# Glucose_Meter_Rev2.net
KiCad netlist of a schematic drawn in EAGLE
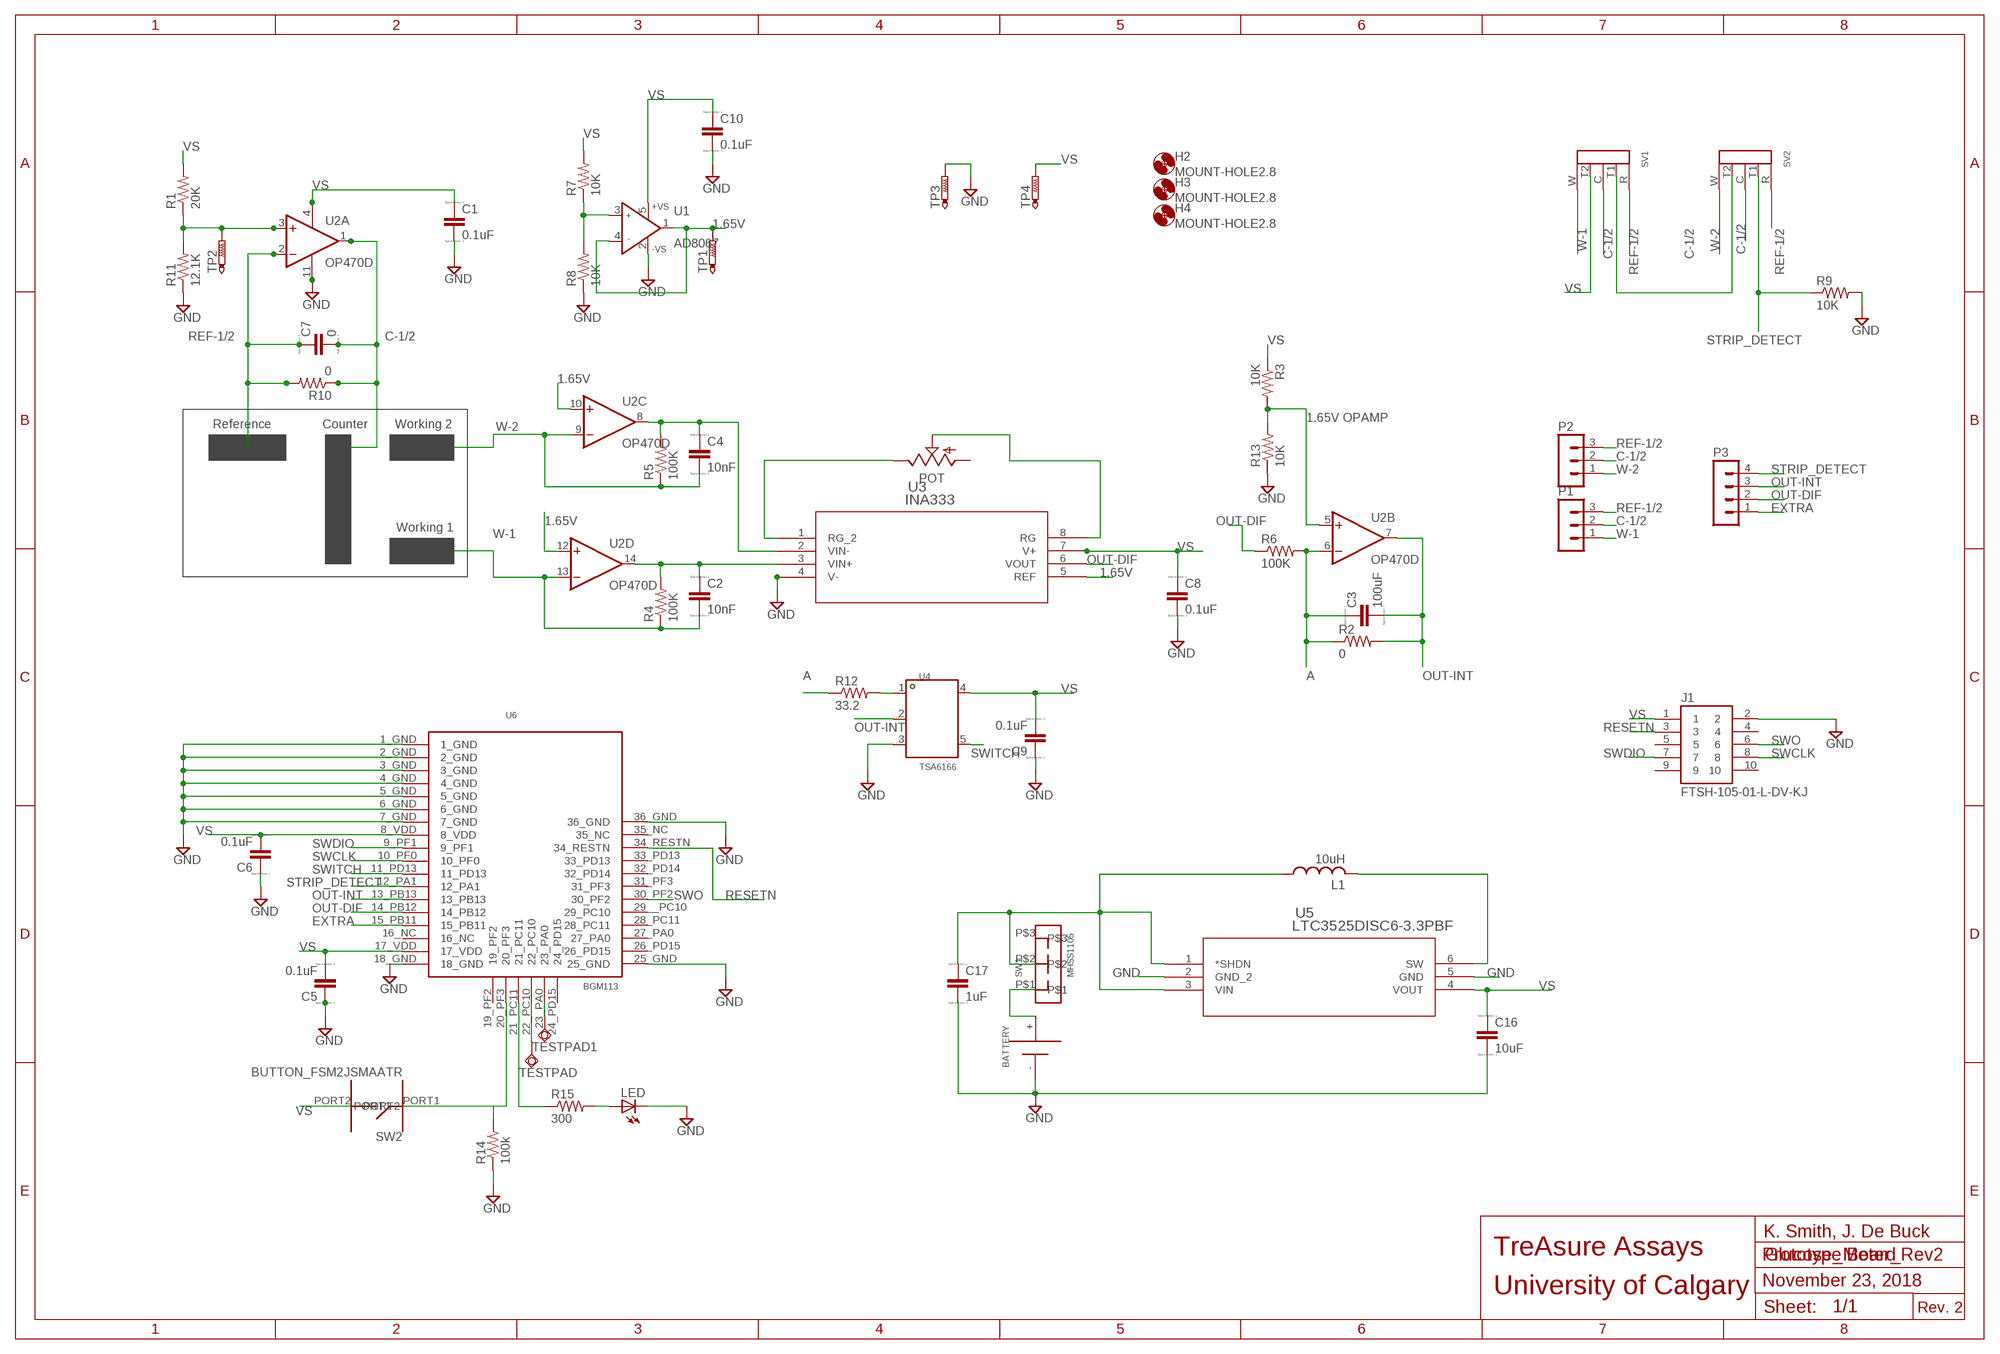
[diagram p0: schematic, sheet 1]

(export (version "E")
  (design (tool "Eeschema 10.0.6"))
  (components
    (comp (ref "BATTERY")
      (value "SMTU2032")
      (footprint "eagle-import:SMTU2032")
      (libsource (lib "eagle-import") (part "SMTU2032"))
    )
    (comp (ref "C1")
      (value "0.1uF")
      (footprint "eagle-import:C0805")
      (libsource (lib "eagle-import") (part "C"))
    )
    (comp (ref "C2")
      (value "10nF")
      (footprint "eagle-import:C0805")
      (libsource (lib "eagle-import") (part "C"))
    )
    (comp (ref "C3")
      (value "100uF")
      (footprint "eagle-import:C1210")
      (libsource (lib "eagle-import") (part "CC1210"))
    )
    (comp (ref "C4")
      (value "10nF")
      (footprint "eagle-import:C0805")
      (libsource (lib "eagle-import") (part "C"))
    )
    (comp (ref "C5")
      (value "0.1uF")
      (footprint "eagle-import:C0805")
      (libsource (lib "eagle-import") (part "C"))
    )
    (comp (ref "C6")
      (value "0.1uF")
      (footprint "eagle-import:C0805")
      (libsource (lib "eagle-import") (part "C"))
    )
    (comp (ref "C7") (value "0") (footprint "eagle-import:C0805") (libsource (lib "eagle-import") (part "C")))
    (comp (ref "C8")
      (value "0.1uF")
      (footprint "eagle-import:C0805")
      (libsource (lib "eagle-import") (part "C"))
    )
    (comp (ref "C9")
      (value "0.1uF")
      (footprint "eagle-import:C0805")
      (libsource (lib "eagle-import") (part "C"))
    )
    (comp (ref "C10")
      (value "0.1uF")
      (footprint "eagle-import:C0805")
      (libsource (lib "eagle-import") (part "C"))
    )
    (comp (ref "C16")
      (value "10uF")
      (footprint "eagle-import:C0805")
      (libsource (lib "eagle-import") (part "C"))
    )
    (comp (ref "C17")
      (value "1uF")
      (footprint "eagle-import:C0805")
      (libsource (lib "eagle-import") (part "C"))
    )
    (comp (ref "H2")
      (value "MOUNT-HOLE2.8")
      (footprint "eagle-import:2,8")
      (libsource (lib "eagle-import") (part "MOUNT-HOLE2.8"))
    )
    (comp (ref "H3")
      (value "MOUNT-HOLE2.8")
      (footprint "eagle-import:2,8")
      (libsource (lib "eagle-import") (part "MOUNT-HOLE2.8"))
    )
    (comp (ref "H4")
      (value "MOUNT-HOLE2.8")
      (footprint "eagle-import:2,8")
      (libsource (lib "eagle-import") (part "MOUNT-HOLE2.8"))
    )
    (comp (ref "J1")
      (value "FTSH-105-01-L-DV-KJ")
      (footprint "eagle-import:SAMTEC_FTSH-105-01-L-DV-K")
      (fields (field (name "MF") "Samtec Inc.") (field (name "MP") "FTSH-105-01-L-DV-K"))
      (libsource (lib "eagle-import") (part "FTSH-105-01-L-DV-KJ"))
    )
    (comp (ref "L1")
      (value "10uH")
      (footprint "eagle-import:L3225M")
      (libsource (lib "eagle-import") (part "L-USL3225M"))
    )
    (comp (ref "LED")
      (value "LED3MM")
      (footprint "eagle-import:LED3MM")
      (libsource (lib "eagle-import") (part "LED3MM"))
    )
    (comp (ref "P1")
      (value "MA03-1")
      (footprint "eagle-import:MA03-1")
      (libsource (lib "eagle-import") (part "MA03-1"))
    )
    (comp (ref "P2")
      (value "MA03-1")
      (footprint "eagle-import:MA03-1")
      (libsource (lib "eagle-import") (part "MA03-1"))
    )
    (comp (ref "P3")
      (value "MA04-1")
      (footprint "eagle-import:MA04-1")
      (libsource (lib "eagle-import") (part "MA04-1"))
    )
    (comp (ref "POT")
      (value "TRIM_US-RJ9W")
      (footprint "eagle-import:RJ9W")
      (libsource (lib "eagle-import") (part "TRIM_US-RJ9W"))
    )
    (comp (ref "R1")
      (value "20K")
      (footprint "eagle-import:R0805")
      (libsource (lib "eagle-import") (part "R-US_R0805"))
    )
    (comp (ref "R2")
      (value "0")
      (footprint "eagle-import:R0805")
      (libsource (lib "eagle-import") (part "R-US_R0805"))
    )
    (comp (ref "R3")
      (value "10K")
      (footprint "eagle-import:R0805")
      (libsource (lib "eagle-import") (part "R-US_R0805"))
    )
    (comp (ref "R4")
      (value "100K")
      (footprint "eagle-import:R0805")
      (libsource (lib "eagle-import") (part "R-US_R0805"))
    )
    (comp (ref "R5")
      (value "100K")
      (footprint "eagle-import:R0805")
      (libsource (lib "eagle-import") (part "R-US_R0805"))
    )
    (comp (ref "R6")
      (value "100K")
      (footprint "eagle-import:R0805")
      (libsource (lib "eagle-import") (part "R-US_R0805"))
    )
    (comp (ref "R7")
      (value "10K")
      (footprint "eagle-import:R0805")
      (libsource (lib "eagle-import") (part "R-US_R0805"))
    )
    (comp (ref "R8")
      (value "10K")
      (footprint "eagle-import:R0805")
      (libsource (lib "eagle-import") (part "R-US_R0805"))
    )
    (comp (ref "R9")
      (value "10K")
      (footprint "eagle-import:R0805")
      (libsource (lib "eagle-import") (part "R-US_R0805"))
    )
    (comp (ref "R10")
      (value "0")
      (footprint "eagle-import:R0805")
      (libsource (lib "eagle-import") (part "R-US_R0805"))
    )
    (comp (ref "R11")
      (value "12.1K")
      (footprint "eagle-import:R0805")
      (libsource (lib "eagle-import") (part "R-US_R0805"))
    )
    (comp (ref "R12")
      (value "33.2")
      (footprint "eagle-import:R0805")
      (libsource (lib "eagle-import") (part "R-US_R0805"))
    )
    (comp (ref "R13")
      (value "10K")
      (footprint "eagle-import:R0805")
      (libsource (lib "eagle-import") (part "R-US_R0805"))
    )
    (comp (ref "R14")
      (value "100k")
      (footprint "eagle-import:R0805")
      (libsource (lib "eagle-import") (part "R-US_R0805"))
    )
    (comp (ref "R15")
      (value "300")
      (footprint "eagle-import:R0805")
      (libsource (lib "eagle-import") (part "R-US_R0805"))
    )
    (comp (ref "SV1")
      (value "SW-JS-05")
      (footprint "eagle-import:SW-JS-05")
      (libsource (lib "eagle-import") (part "SW-JS-05"))
    )
    (comp (ref "SV2")
      (value "SW-JS-05")
      (footprint "eagle-import:SW-JS-05")
      (libsource (lib "eagle-import") (part "SW-JS-05"))
    )
    (comp (ref "SW1")
      (value "MHSS1105")
      (footprint "eagle-import:MHSS1105")
      (libsource (lib "eagle-import") (part "MHSS1105"))
    )
    (comp (ref "SW2")
      (value "BUTTON_FSM2JSMAATR")
      (footprint "eagle-import:BUTTON_FSM2JSMAATR")
      (libsource (lib "eagle-import") (part "BUTTON_FSM2JSMAATR"))
    )
    (comp (ref "TESTPAD")
      (value "TPSQTP06R")
      (footprint "eagle-import:TP06R")
      (libsource (lib "eagle-import") (part "TPSQTP06R"))
    )
    (comp (ref "TESTPAD1")
      (value "TPSQTP06R")
      (footprint "eagle-import:TP06R")
      (libsource (lib "eagle-import") (part "TPSQTP06R"))
    )
    (comp (ref "TP1")
      (value "PTR1PAD1-13")
      (footprint "eagle-import:P1-13")
      (libsource (lib "eagle-import") (part "PTR1PAD1-13"))
    )
    (comp (ref "TP2")
      (value "PTR1PAD1-13")
      (footprint "eagle-import:P1-13")
      (libsource (lib "eagle-import") (part "PTR1PAD1-13"))
    )
    (comp (ref "TP3")
      (value "PTR1PAD1-13")
      (footprint "eagle-import:P1-13")
      (libsource (lib "eagle-import") (part "PTR1PAD1-13"))
    )
    (comp (ref "TP4")
      (value "PTR1PAD1-13")
      (footprint "eagle-import:P1-13")
      (libsource (lib "eagle-import") (part "PTR1PAD1-13"))
    )
    (comp (ref "U1")
      (value "AD8067")
      (footprint "eagle-import:SOT23-5")
      (fields (field (name "MF") "ALTERA CORPORATION") (field (name "MPN") "AD8067ARTZ-REEL7"))
      (libsource (lib "eagle-import") (part "AD8067"))
    )
    (comp (ref "U2")
      (value "OP470D")
      (footprint "eagle-import:SO14")
      (libsource (lib "eagle-import") (part "OP470D"))
    )
    (comp (ref "U3")
      (value "INA333")
      (footprint "eagle-import:DGK8")
      (fields
        (field (name "MANUFACTURER") "Texas Instruments")
        (field (name "MANUFACTURER_PART_NUMBER") "ina333_dgk_8")
      )
      (libsource (lib "eagle-import") (part "INA333_DGK_8"))
    )
    (comp (ref "U4")
      (value "TSA6166")
      (footprint "eagle-import:SOT23-5")
      (libsource (lib "eagle-import") (part "TSA6166"))
    )
    (comp (ref "U5")
      (value "LTC3525DISC6-3.3PBF")
      (footprint "eagle-import:SC70-SC6")
      (fields (field (name "MANUFACTURER_PART_NUMBER") "ltc3525disc6-3.3#pbf"))
      (libsource (lib "eagle-import") (part "LTC3525DISC6-3.3PBF"))
    )
    (comp (ref "U6")
      (value "BGM113")
      (footprint "eagle-import:BGM113")
      (libsource (lib "eagle-import") (part "BGM113"))
    )
  )
  (nets
    (net (code "1") (name "/1.65V") (class "Default")
      (node (ref "TP1") (pin "TP") (pinfunction "TP_TP") (pintype "input"))
      (node (ref "U1") (pin "1") (pinfunction "OUT_1") (pintype "output"))
      (node (ref "U1") (pin "4") (pinfunction "IN-_4") (pintype "input"))
      (node (ref "U2") (pin "10") (pinfunction "+IN_10") (pintype "input"))
      (node (ref "U2") (pin "12") (pinfunction "+IN_12") (pintype "input"))
      (node (ref "U3") (pin "5") (pinfunction "REF_5") (pintype "passive"))
    )
    (net (code "2") (name "/A") (class "Default")
      (node (ref "C3") (pin "1") (pinfunction "1_1") (pintype "passive"))
      (node (ref "R12") (pin "1") (pinfunction "1_1") (pintype "passive"))
      (node (ref "R2") (pin "1") (pinfunction "1_1") (pintype "passive"))
      (node (ref "R6") (pin "2") (pinfunction "2_2") (pintype "passive"))
      (node (ref "U2") (pin "6") (pinfunction "-IN_6") (pintype "input"))
    )
    (net (code "3") (name "/C-1{slash}2") (class "Default")
      (node (ref "C7") (pin "2") (pinfunction "2_2") (pintype "passive"))
      (node (ref "P1") (pin "2") (pinfunction "2_2") (pintype "passive"))
      (node (ref "P2") (pin "2") (pinfunction "2_2") (pintype "passive"))
      (node (ref "R10") (pin "1") (pinfunction "1_1") (pintype "passive"))
      (node (ref "SV1") (pin "C") (pinfunction "C_C") (pintype "bidirectional"))
      (node (ref "SV2") (pin "C") (pinfunction "C_C") (pintype "bidirectional"))
      (node (ref "U2") (pin "1") (pinfunction "OUT_1") (pintype "output"))
    )
    (net (code "4") (name "/EXTRA") (class "Default")
      (node (ref "P3") (pin "1") (pinfunction "1_1") (pintype "passive"))
      (node (ref "U6") (pin "15_PB11") (pinfunction "15_PB11_15_PB11") (pintype "bidirectional"))
    )
    (net (code "5") (name "/OUT-DIF") (class "Default")
      (node (ref "P3") (pin "2") (pinfunction "2_2") (pintype "passive"))
      (node (ref "R6") (pin "1") (pinfunction "1_1") (pintype "passive"))
      (node (ref "U3") (pin "6") (pinfunction "VOUT_6") (pintype "output"))
      (node (ref "U6") (pin "14_PB12") (pinfunction "14_PB12_14_PB12") (pintype "bidirectional"))
    )
    (net (code "6") (name "/OUT-INT") (class "Default")
      (node (ref "C3") (pin "2") (pinfunction "2_2") (pintype "passive"))
      (node (ref "P3") (pin "3") (pinfunction "3_3") (pintype "passive"))
      (node (ref "R2") (pin "2") (pinfunction "2_2") (pintype "passive"))
      (node (ref "U2") (pin "7") (pinfunction "OUT_7") (pintype "output"))
      (node (ref "U4") (pin "2") (pinfunction "B_2") (pintype "bidirectional"))
      (node (ref "U6") (pin "13_PB13") (pinfunction "13_PB13_13_PB13") (pintype "bidirectional"))
    )
    (net (code "7") (name "/REF-1{slash}2") (class "Default")
      (node (ref "C7") (pin "1") (pinfunction "1_1") (pintype "passive"))
      (node (ref "P1") (pin "3") (pinfunction "3_3") (pintype "passive"))
      (node (ref "P2") (pin "3") (pinfunction "3_3") (pintype "passive"))
      (node (ref "R10") (pin "2") (pinfunction "2_2") (pintype "passive"))
      (node (ref "SV1") (pin "R") (pinfunction "R_R") (pintype "bidirectional"))
      (node (ref "SV2") (pin "R") (pinfunction "R_R") (pintype "bidirectional"))
      (node (ref "U2") (pin "2") (pinfunction "-IN_2") (pintype "input"))
    )
    (net (code "8") (name "/RESETN") (class "Default")
      (node (ref "J1") (pin "3") (pinfunction "3_3") (pintype "passive"))
      (node (ref "U6") (pin "34_RESTN") (pinfunction "34_RESTN_34_RESTN") (pintype "bidirectional"))
    )
    (net (code "9") (name "/STRIP_DETECT") (class "Default")
      (node (ref "P3") (pin "4") (pinfunction "4_4") (pintype "passive"))
      (node (ref "R9") (pin "1") (pinfunction "1_1") (pintype "passive"))
      (node (ref "SV2") (pin "T1") (pinfunction "T1_T1") (pintype "bidirectional"))
      (node (ref "U6") (pin "12_PA1") (pinfunction "12_PA1_12_PA1") (pintype "bidirectional"))
    )
    (net (code "10") (name "/SWCLK") (class "Default")
      (node (ref "J1") (pin "8") (pinfunction "8_8") (pintype "passive"))
      (node (ref "U6") (pin "10_PF0") (pinfunction "10_PF0_10_PF0") (pintype "bidirectional"))
    )
    (net (code "11") (name "/SWDIO") (class "Default")
      (node (ref "J1") (pin "7") (pinfunction "7_7") (pintype "passive"))
      (node (ref "U6") (pin "9_PF1") (pinfunction "9_PF1_9_PF1") (pintype "bidirectional"))
    )
    (net (code "12") (name "/SWITCH") (class "Default")
      (node (ref "U4") (pin "5") (pinfunction "ON/OFF_5") (pintype "bidirectional"))
      (node (ref "U6") (pin "11_PD13") (pinfunction "11_PD13_11_PD13") (pintype "bidirectional"))
    )
    (net (code "13") (name "/SWO") (class "Default")
      (node (ref "J1") (pin "6") (pinfunction "6_6") (pintype "passive"))
      (node (ref "U6") (pin "30_PF2") (pinfunction "30_PF2_30_PF2") (pintype "bidirectional"))
    )
    (net (code "14") (name "/VS") (class "Default")
      (node (ref "C1") (pin "1") (pinfunction "1_1") (pintype "passive"))
      (node (ref "C10") (pin "1") (pinfunction "1_1") (pintype "passive"))
      (node (ref "C16") (pin "1") (pinfunction "1_1") (pintype "passive"))
      (node (ref "C5") (pin "2") (pinfunction "2_2") (pintype "passive"))
      (node (ref "C6") (pin "2") (pinfunction "2_2") (pintype "passive"))
      (node (ref "C8") (pin "1") (pinfunction "1_1") (pintype "passive"))
      (node (ref "C9") (pin "2") (pinfunction "2_2") (pintype "passive"))
      (node (ref "J1") (pin "1") (pinfunction "1_1") (pintype "passive"))
      (node (ref "R1") (pin "2") (pinfunction "2_2") (pintype "passive"))
      (node (ref "R3") (pin "1") (pinfunction "1_1") (pintype "passive"))
      (node (ref "R7") (pin "2") (pinfunction "2_2") (pintype "passive"))
      (node (ref "SV1") (pin "T2") (pinfunction "T2_T2") (pintype "bidirectional"))
      (node (ref "SW2") (pin "PORT2") (pinfunction "PORT2_PORT2") (pintype "bidirectional"))
      (node (ref "TP4") (pin "TP") (pinfunction "TP_TP") (pintype "input"))
      (node (ref "U1") (pin "5") (pinfunction "+VS_5") (pintype "input"))
      (node (ref "U2") (pin "4") (pinfunction "V+_4") (pintype "power_in"))
      (node (ref "U3") (pin "7") (pinfunction "V+_7") (pintype "power_in"))
      (node (ref "U4") (pin "4") (pinfunction "VS_4") (pintype "bidirectional"))
      (node (ref "U5") (pin "4") (pinfunction "VOUT_4") (pintype "output"))
      (node (ref "U6") (pin "17_VDD") (pinfunction "17_VDD_17_VDD") (pintype "bidirectional"))
      (node (ref "U6") (pin "8_VDD") (pinfunction "8_VDD_8_VDD") (pintype "bidirectional"))
    )
    (net (code "15") (name "/W-1") (class "Default")
      (node (ref "C2") (pin "2") (pinfunction "2_2") (pintype "passive"))
      (node (ref "P1") (pin "1") (pinfunction "1_1") (pintype "passive"))
      (node (ref "R4") (pin "1") (pinfunction "1_1") (pintype "passive"))
      (node (ref "SV1") (pin "W") (pinfunction "W_W") (pintype "bidirectional"))
      (node (ref "U2") (pin "13") (pinfunction "-IN_13") (pintype "input"))
    )
    (net (code "16") (name "/W-2") (class "Default")
      (node (ref "C4") (pin "2") (pinfunction "2_2") (pintype "passive"))
      (node (ref "P2") (pin "1") (pinfunction "1_1") (pintype "passive"))
      (node (ref "R5") (pin "1") (pinfunction "1_1") (pintype "passive"))
      (node (ref "SV2") (pin "W") (pinfunction "W_W") (pintype "bidirectional"))
      (node (ref "U2") (pin "9") (pinfunction "-IN_9") (pintype "input"))
    )
    (net (code "17") (name "GND") (class "Default")
      (node (ref "BATTERY") (pin "-") (pinfunction "-_-") (pintype "power_in"))
      (node (ref "C1") (pin "2") (pinfunction "2_2") (pintype "passive"))
      (node (ref "C10") (pin "2") (pinfunction "2_2") (pintype "passive"))
      (node (ref "C16") (pin "2") (pinfunction "2_2") (pintype "passive"))
      (node (ref "C17") (pin "2") (pinfunction "2_2") (pintype "passive"))
      (node (ref "C5") (pin "1") (pinfunction "1_1") (pintype "passive"))
      (node (ref "C6") (pin "1") (pinfunction "1_1") (pintype "passive"))
      (node (ref "C8") (pin "2") (pinfunction "2_2") (pintype "passive"))
      (node (ref "C9") (pin "1") (pinfunction "1_1") (pintype "passive"))
      (node (ref "J1") (pin "2") (pinfunction "2_2") (pintype "passive"))
      (node (ref "LED") (pin "K") (pinfunction "C_K") (pintype "passive"))
      (node (ref "R11") (pin "1") (pinfunction "1_1") (pintype "passive"))
      (node (ref "R13") (pin "1") (pinfunction "1_1") (pintype "passive"))
      (node (ref "R14") (pin "1") (pinfunction "1_1") (pintype "passive"))
      (node (ref "R8") (pin "1") (pinfunction "1_1") (pintype "passive"))
      (node (ref "R9") (pin "2") (pinfunction "2_2") (pintype "passive"))
      (node (ref "TP3") (pin "TP") (pinfunction "TP_TP") (pintype "input"))
      (node (ref "U1") (pin "2") (pinfunction "-VS_2") (pintype "input"))
      (node (ref "U2") (pin "11") (pinfunction "V-_11") (pintype "power_in"))
      (node (ref "U3") (pin "4") (pinfunction "V-_4") (pintype "power_in"))
      (node (ref "U4") (pin "3") (pinfunction "GND_3") (pintype "bidirectional"))
      (node (ref "U5") (pin "2") (pinfunction "GND_2_2") (pintype "power_in"))
      (node (ref "U5") (pin "5") (pinfunction "GND_5") (pintype "power_in"))
      (node (ref "U6") (pin "18_GND") (pinfunction "18_GND_18_GND") (pintype "bidirectional"))
      (node (ref "U6") (pin "1_GND") (pinfunction "1_GND_1_GND") (pintype "bidirectional"))
      (node (ref "U6") (pin "25_GND") (pinfunction "25_GND_25_GND") (pintype "bidirectional"))
      (node (ref "U6") (pin "2_GND") (pinfunction "2_GND_2_GND") (pintype "bidirectional"))
      (node (ref "U6") (pin "36_GND") (pinfunction "36_GND_36_GND") (pintype "bidirectional"))
      (node (ref "U6") (pin "3_GND") (pinfunction "3_GND_3_GND") (pintype "bidirectional"))
      (node (ref "U6") (pin "4_GND") (pinfunction "4_GND_4_GND") (pintype "bidirectional"))
      (node (ref "U6") (pin "5_GND") (pinfunction "5_GND_5_GND") (pintype "bidirectional"))
      (node (ref "U6") (pin "6_GND") (pinfunction "6_GND_6_GND") (pintype "bidirectional"))
      (node (ref "U6") (pin "7_GND") (pinfunction "7_GND_7_GND") (pintype "bidirectional"))
    )
    (net (code "18") (name "Net-(BATTERY-Pad+)") (class "Default")
      (node (ref "BATTERY") (pin "+") (pinfunction "+_+") (pintype "power_in"))
      (node (ref "SW1") (pin "P$1") (pinfunction "P$1_P$1") (pintype "bidirectional"))
    )
    (net (code "19") (name "Net-(LED-PadA)") (class "Default")
      (node (ref "LED") (pin "A") (pinfunction "A_A") (pintype "passive"))
      (node (ref "R15") (pin "2") (pinfunction "2_2") (pintype "passive"))
    )
    (net (code "20") (name "Net-(R14-Pad2)") (class "Default")
      (node (ref "R14") (pin "2") (pinfunction "2_2") (pintype "passive"))
      (node (ref "SW2") (pin "PORT1") (pinfunction "PORT1_PORT1") (pintype "bidirectional"))
      (node (ref "U6") (pin "20_PF3") (pinfunction "20_PF3_20_PF3") (pintype "bidirectional"))
    )
    (net (code "21") (name "Net-(R15-Pad1)") (class "Default")
      (node (ref "R15") (pin "1") (pinfunction "1_1") (pintype "passive"))
      (node (ref "U6") (pin "21_PC11") (pinfunction "21_PC11_21_PC11") (pintype "bidirectional"))
    )
    (net (code "22") (name "Net-(SV1-PadT1)") (class "Default")
      (node (ref "SV1") (pin "T1") (pinfunction "T1_T1") (pintype "bidirectional"))
      (node (ref "SV2") (pin "T2") (pinfunction "T2_T2") (pintype "bidirectional"))
    )
    (net (code "23") (name "Net-(TESTPAD-PadTP)") (class "Default")
      (node (ref "TESTPAD") (pin "TP") (pinfunction "TP_TP") (pintype "input"))
      (node (ref "U6") (pin "22_PC10") (pinfunction "22_PC10_22_PC10") (pintype "bidirectional"))
    )
    (net (code "24") (name "Net-(TESTPAD1-PadTP)") (class "Default")
      (node (ref "TESTPAD1") (pin "TP") (pinfunction "TP_TP") (pintype "input"))
      (node (ref "U6") (pin "23_PA0") (pinfunction "23_PA0_23_PA0") (pintype "bidirectional"))
    )
    (net (code "25") (name "Net-(U1-IN+)") (class "Default")
      (node (ref "R7") (pin "1") (pinfunction "1_1") (pintype "passive"))
      (node (ref "R8") (pin "2") (pinfunction "2_2") (pintype "passive"))
      (node (ref "U1") (pin "3") (pinfunction "IN+_3") (pintype "input"))
    )
    (net (code "26") (name "Net-(U2A-+IN)") (class "Default")
      (node (ref "R1") (pin "1") (pinfunction "1_1") (pintype "passive"))
      (node (ref "R11") (pin "2") (pinfunction "2_2") (pintype "passive"))
      (node (ref "TP2") (pin "TP") (pinfunction "TP_TP") (pintype "input"))
      (node (ref "U2") (pin "3") (pinfunction "+IN_3") (pintype "input"))
    )
    (net (code "27") (name "Net-(U2B-+IN)") (class "Default")
      (node (ref "R13") (pin "2") (pinfunction "2_2") (pintype "passive"))
      (node (ref "R3") (pin "2") (pinfunction "2_2") (pintype "passive"))
      (node (ref "U2") (pin "5") (pinfunction "+IN_5") (pintype "input"))
    )
    (net (code "28") (name "Net-(U2C-OUT)") (class "Default")
      (node (ref "C4") (pin "1") (pinfunction "1_1") (pintype "passive"))
      (node (ref "R5") (pin "2") (pinfunction "2_2") (pintype "passive"))
      (node (ref "U2") (pin "8") (pinfunction "OUT_8") (pintype "output"))
      (node (ref "U3") (pin "2") (pinfunction "VIN-_2") (pintype "input"))
    )
    (net (code "29") (name "Net-(U2D-OUT)") (class "Default")
      (node (ref "C2") (pin "1") (pinfunction "1_1") (pintype "passive"))
      (node (ref "R4") (pin "2") (pinfunction "2_2") (pintype "passive"))
      (node (ref "U2") (pin "14") (pinfunction "OUT_14") (pintype "output"))
      (node (ref "U3") (pin "3") (pinfunction "VIN+_3") (pintype "input"))
    )
    (net (code "30") (name "Net-(U3-RG)") (class "Default")
      (node (ref "POT") (pin "S") (pinfunction "S_S") (pintype "passive"))
      (node (ref "U3") (pin "8") (pinfunction "RG_8") (pintype "passive"))
    )
    (net (code "31") (name "Net-(U3-RG_2)") (class "Default")
      (node (ref "POT") (pin "E") (pinfunction "E_E") (pintype "passive"))
      (node (ref "U3") (pin "1") (pinfunction "RG_2_1") (pintype "passive"))
    )
    (net (code "32") (name "Net-(U4-A)") (class "Default")
      (node (ref "R12") (pin "2") (pinfunction "2_2") (pintype "passive"))
      (node (ref "U4") (pin "1") (pinfunction "A_1") (pintype "bidirectional"))
    )
    (net (code "33") (name "Net-(U5-*SHDN)") (class "Default")
      (node (ref "C17") (pin "1") (pinfunction "1_1") (pintype "passive"))
      (node (ref "L1") (pin "1") (pinfunction "1_1") (pintype "passive"))
      (node (ref "SW1") (pin "P$2") (pinfunction "P$2_P$2") (pintype "bidirectional"))
      (node (ref "U5") (pin "1") (pinfunction "*SHDN_1") (pintype "input"))
      (node (ref "U5") (pin "3") (pinfunction "VIN_3") (pintype "input"))
    )
    (net (code "34") (name "Net-(U5-SW)") (class "Default")
      (node (ref "L1") (pin "2") (pinfunction "2_2") (pintype "passive"))
      (node (ref "U5") (pin "6") (pinfunction "SW_6") (pintype "passive"))
    )
    (net (code "35") (name "unconnected-(J1-Pad4)") (class "Default")
      (node (ref "J1") (pin "4") (pinfunction "4_4") (pintype "passive"))
    )
    (net (code "36") (name "unconnected-(J1-Pad5)") (class "Default")
      (node (ref "J1") (pin "5") (pinfunction "5_5") (pintype "passive"))
    )
    (net (code "37") (name "unconnected-(J1-Pad9)") (class "Default")
      (node (ref "J1") (pin "9") (pinfunction "9_9") (pintype "passive"))
    )
    (net (code "38") (name "unconnected-(J1-Pad10)") (class "Default")
      (node (ref "J1") (pin "10") (pinfunction "10_10") (pintype "passive"))
    )
    (net (code "39") (name "unconnected-(POT-PadA)") (class "Default")
      (node (ref "POT") (pin "A") (pinfunction "A_A") (pintype "passive"))
    )
    (net (code "40") (name "unconnected-(SW1-PadP$3)") (class "Default")
      (node (ref "SW1") (pin "P$3") (pinfunction "P$3_P$3") (pintype "bidirectional"))
    )
    (net (code "41") (name "unconnected-(U6-29_PC10-Pad29__PC10)") (class "Default")
      (node (ref "U6") (pin "29__PC10") (pinfunction "29_PC10_29__PC10") (pintype "bidirectional"))
    )
    (net (code "42") (name "unconnected-(U6-Pad16_NC)") (class "Default")
      (node (ref "U6") (pin "16_NC") (pinfunction "16_NC_16_NC") (pintype "bidirectional"))
    )
    (net (code "43") (name "unconnected-(U6-Pad19_PF2)") (class "Default")
      (node (ref "U6") (pin "19_PF2") (pinfunction "19_PF2_19_PF2") (pintype "bidirectional"))
    )
    (net (code "44") (name "unconnected-(U6-Pad24_PD15)") (class "Default")
      (node (ref "U6") (pin "24_PD15") (pinfunction "24_PD15_24_PD15") (pintype "bidirectional"))
    )
    (net (code "45") (name "unconnected-(U6-Pad26_PD15)") (class "Default")
      (node (ref "U6") (pin "26_PD15") (pinfunction "26_PD15_26_PD15") (pintype "bidirectional"))
    )
    (net (code "46") (name "unconnected-(U6-Pad27_PA0)") (class "Default")
      (node (ref "U6") (pin "27_PA0") (pinfunction "27_PA0_27_PA0") (pintype "bidirectional"))
    )
    (net (code "47") (name "unconnected-(U6-Pad28_PC11)") (class "Default")
      (node (ref "U6") (pin "28_PC11") (pinfunction "28_PC11_28_PC11") (pintype "bidirectional"))
    )
    (net (code "48") (name "unconnected-(U6-Pad31_PF3)") (class "Default")
      (node (ref "U6") (pin "31_PF3") (pinfunction "31_PF3_31_PF3") (pintype "bidirectional"))
    )
    (net (code "49") (name "unconnected-(U6-Pad32_PD14)") (class "Default")
      (node (ref "U6") (pin "32_PD14") (pinfunction "32_PD14_32_PD14") (pintype "bidirectional"))
    )
    (net (code "50") (name "unconnected-(U6-Pad33_PD13)") (class "Default")
      (node (ref "U6") (pin "33_PD13") (pinfunction "33_PD13_33_PD13") (pintype "bidirectional"))
    )
    (net (code "51") (name "unconnected-(U6-Pad35_NC)") (class "Default")
      (node (ref "U6") (pin "35_NC") (pinfunction "35_NC_35_NC") (pintype "bidirectional"))
    )
  )
)
